# Main.net
KiCad netlist of a schematic drawn in Altium Designer
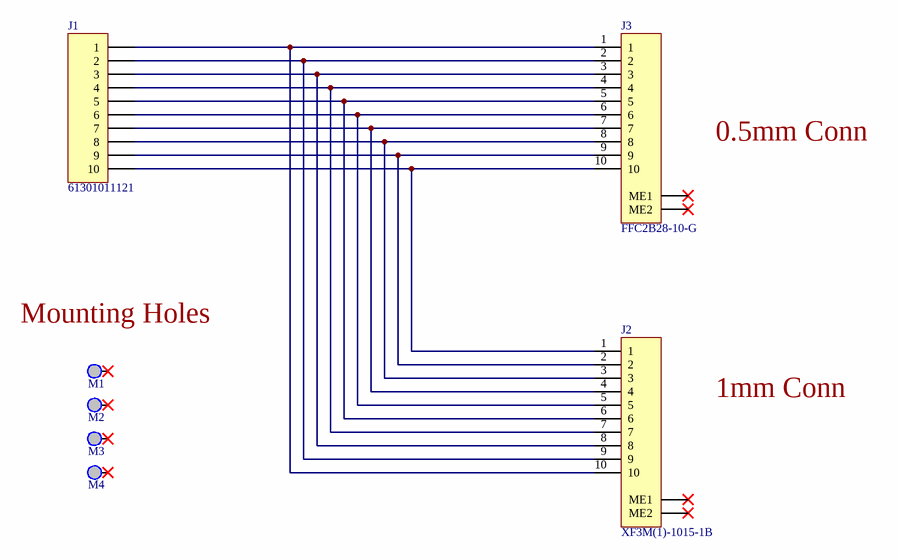
[diagram p0: Main.SchDoc]

(export (version "E")
  (design (tool "Eeschema 10.0.6"))
  (components
    (comp (ref "J1")
      (value "61301011121")
      (footprint "HDR-V-10P-2.54MM")
      (description "THT Vertical Pin Header WR-PHD, Pitch 2.54 mm, Single Row, 10 pins")
      (libsource (lib "intercreate") (part "HDR-V-1X10-M-2.54MM"))
    )
    (comp (ref "J2")
      (value "XF3M(1)-1015-1B")
      (footprint "CONN-FFC-H-10P-1MM")
      (description "1.0-mm Pitch, Dual Contact ; For FPC/FFC, 10 Contacts, RoHS")
      (libsource (lib "intercreate") (part "CONN-FFC-H-10P-1MM"))
    )
    (comp (ref "J3")
      (value "FFC2B28-10-G")
      (footprint "CONN-FFC-H-10P-0.5MM")
      (libsource (lib "intercreate") (part "CONN-FFC-H-10P-0.5MM"))
    )
    (comp (ref "M1")
      (value "MTG_HOLE")
      (footprint "MH_P_2.5MM")
      (description "MTG HOLE PLATED VARIOUS SIZES")
      (libsource (lib "intercreate") (part "MTG_HOLE"))
    )
    (comp (ref "M2")
      (value "MTG_HOLE")
      (footprint "MH_P_2.5MM")
      (description "MTG HOLE PLATED VARIOUS SIZES")
      (libsource (lib "intercreate") (part "MTG_HOLE"))
    )
    (comp (ref "M3")
      (value "MTG_HOLE")
      (footprint "MH_P_2.5MM")
      (description "MTG HOLE PLATED VARIOUS SIZES")
      (libsource (lib "intercreate") (part "MTG_HOLE"))
    )
    (comp (ref "M4")
      (value "MTG_HOLE")
      (footprint "MH_P_2.5MM")
      (description "MTG HOLE PLATED VARIOUS SIZES")
      (libsource (lib "intercreate") (part "MTG_HOLE"))
    )
  )
  (nets
    (net (code "1") (name "Net-(J1-Pad1)") (class "Default")
      (node (ref "J1") (pin "1") (pinfunction "1_1") (pintype "passive"))
      (node (ref "J2") (pin "10") (pinfunction "10_10") (pintype "passive"))
      (node (ref "J3") (pin "1") (pinfunction "1_1") (pintype "passive"))
    )
    (net (code "2") (name "Net-(J1-Pad2)") (class "Default")
      (node (ref "J1") (pin "2") (pinfunction "2_2") (pintype "passive"))
      (node (ref "J2") (pin "9") (pinfunction "9_9") (pintype "passive"))
      (node (ref "J3") (pin "2") (pinfunction "2_2") (pintype "passive"))
    )
    (net (code "3") (name "Net-(J1-Pad3)") (class "Default")
      (node (ref "J1") (pin "3") (pinfunction "3_3") (pintype "passive"))
      (node (ref "J2") (pin "8") (pinfunction "8_8") (pintype "passive"))
      (node (ref "J3") (pin "3") (pinfunction "3_3") (pintype "passive"))
    )
    (net (code "4") (name "Net-(J1-Pad4)") (class "Default")
      (node (ref "J1") (pin "4") (pinfunction "4_4") (pintype "passive"))
      (node (ref "J2") (pin "7") (pinfunction "7_7") (pintype "passive"))
      (node (ref "J3") (pin "4") (pinfunction "4_4") (pintype "passive"))
    )
    (net (code "5") (name "Net-(J1-Pad5)") (class "Default")
      (node (ref "J1") (pin "5") (pinfunction "5_5") (pintype "passive"))
      (node (ref "J2") (pin "6") (pinfunction "6_6") (pintype "passive"))
      (node (ref "J3") (pin "5") (pinfunction "5_5") (pintype "passive"))
    )
    (net (code "6") (name "Net-(J1-Pad6)") (class "Default")
      (node (ref "J1") (pin "6") (pinfunction "6_6") (pintype "passive"))
      (node (ref "J2") (pin "5") (pinfunction "5_5") (pintype "passive"))
      (node (ref "J3") (pin "6") (pinfunction "6_6") (pintype "passive"))
    )
    (net (code "7") (name "Net-(J1-Pad7)") (class "Default")
      (node (ref "J1") (pin "7") (pinfunction "7_7") (pintype "passive"))
      (node (ref "J2") (pin "4") (pinfunction "4_4") (pintype "passive"))
      (node (ref "J3") (pin "7") (pinfunction "7_7") (pintype "passive"))
    )
    (net (code "8") (name "Net-(J1-Pad8)") (class "Default")
      (node (ref "J1") (pin "8") (pinfunction "8_8") (pintype "passive"))
      (node (ref "J2") (pin "3") (pinfunction "3_3") (pintype "passive"))
      (node (ref "J3") (pin "8") (pinfunction "8_8") (pintype "passive"))
    )
    (net (code "9") (name "Net-(J1-Pad9)") (class "Default")
      (node (ref "J1") (pin "9") (pinfunction "9_9") (pintype "passive"))
      (node (ref "J2") (pin "2") (pinfunction "2_2") (pintype "passive"))
      (node (ref "J3") (pin "9") (pinfunction "9_9") (pintype "passive"))
    )
    (net (code "10") (name "Net-(J1-Pad10)") (class "Default")
      (node (ref "J1") (pin "10") (pinfunction "10_10") (pintype "passive"))
      (node (ref "J2") (pin "1") (pinfunction "1_1") (pintype "passive"))
      (node (ref "J3") (pin "10") (pinfunction "10_10") (pintype "passive"))
    )
    (net (code "11") (name "unconnected-(J2-PadME1)") (class "Default")
      (node (ref "J2") (pin "ME1") (pinfunction "ME1_ME1") (pintype "passive+no_connect"))
    )
    (net (code "12") (name "unconnected-(J2-PadME2)") (class "Default")
      (node (ref "J2") (pin "ME2") (pinfunction "ME2_ME2") (pintype "passive+no_connect"))
    )
    (net (code "13") (name "unconnected-(J3-PadME1)") (class "Default")
      (node (ref "J3") (pin "ME1") (pinfunction "ME1_ME1") (pintype "passive+no_connect"))
    )
    (net (code "14") (name "unconnected-(J3-PadME2)") (class "Default")
      (node (ref "J3") (pin "ME2") (pinfunction "ME2_ME2") (pintype "passive+no_connect"))
    )
    (net (code "15") (name "unconnected-(M1-Pad1)") (class "Default")
      (node (ref "M1") (pin "1") (pinfunction "1_1") (pintype "passive+no_connect"))
    )
    (net (code "16") (name "unconnected-(M2-Pad1)") (class "Default")
      (node (ref "M2") (pin "1") (pinfunction "1_1") (pintype "passive+no_connect"))
    )
    (net (code "17") (name "unconnected-(M3-Pad1)") (class "Default")
      (node (ref "M3") (pin "1") (pinfunction "1_1") (pintype "passive+no_connect"))
    )
    (net (code "18") (name "unconnected-(M4-Pad1)") (class "Default")
      (node (ref "M4") (pin "1") (pinfunction "1_1") (pintype "passive+no_connect"))
    )
  )
)
